# main.net
KiCad netlist of a schematic drawn in Altium Designer
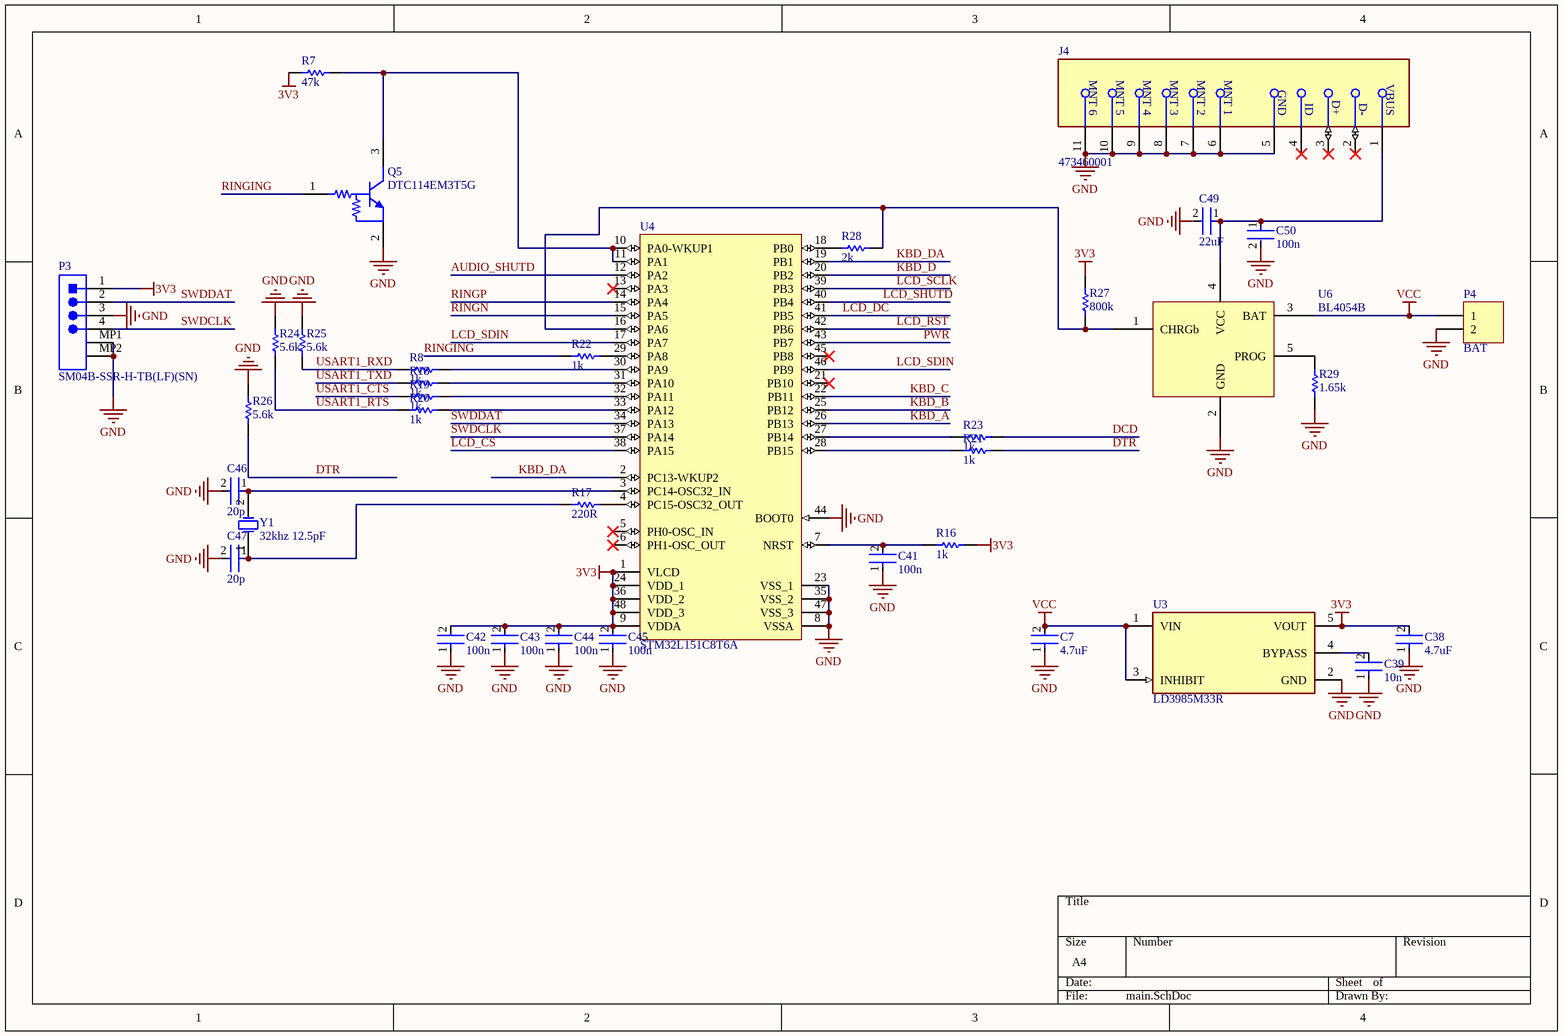
[diagram p0: main.SchDoc]

(export (version "E")
  (design (tool "Eeschema 10.0.6"))
  (components
    (comp (ref "C7")
      (value "4.7uF")
      (footprint "FP-GRM188-0_1-e0_2_0_55-IPC_A")
      (description "Chip Multilayer Ceramic Capacitors for General Purpose, 0603, 10uF, X5R, 15%, 20%, 6.3V")
      (fields (field (name "VOLTAGE") "6.3V") (field (name "TOLERANCE") "20%"))
      (libsource (lib "Altium Content Vault") (part "02cd4be3c70576c341d710602a673aa"))
    )
    (comp (ref "C38")
      (value "4.7uF")
      (footprint "FP-GRM188-0_1-e0_2_0_55-IPC_A")
      (description "Chip Multilayer Ceramic Capacitors for General Purpose, 0603, 10uF, X5R, 15%, 20%, 6.3V")
      (fields (field (name "VOLTAGE") "6.3V") (field (name "TOLERANCE") "20%"))
      (libsource (lib "Altium Content Vault") (part "02cd4be3c70576c341d710602a673aa"))
    )
    (comp (ref "C39")
      (value "10n")
      (footprint "FP-GRM155-0_05-IPC_A")
      (description "Chip Multilayer Ceramic Capacitors for General Purpose, 0402, 470pF, C0G, 30ppm/°C, 5%, 50V")
      (fields (field (name "VOLTAGE") "50V") (field (name "TOLERANCE") "5%"))
      (libsource (lib "Altium Content Vault") (part "02cd4be3c70576c341d710602a673aa"))
    )
    (comp (ref "C41")
      (value "100n")
      (footprint "FP-GRM155-0_05-IPC_A")
      (description "Chip Multilayer Ceramic Capacitors for General Purpose, 0402, 470pF, C0G, 30ppm/°C, 5%, 50V")
      (fields (field (name "VOLTAGE") "50V") (field (name "TOLERANCE") "5%"))
      (libsource (lib "Altium Content Vault") (part "02cd4be3c70576c341d710602a673aa"))
    )
    (comp (ref "C42")
      (value "100n")
      (footprint "FP-GRM155-0_05-IPC_A")
      (description "Chip Multilayer Ceramic Capacitors for General Purpose, 0402, 470pF, C0G, 30ppm/°C, 5%, 50V")
      (fields (field (name "VOLTAGE") "50V") (field (name "TOLERANCE") "5%"))
      (libsource (lib "Altium Content Vault") (part "02cd4be3c70576c341d710602a673aa"))
    )
    (comp (ref "C43")
      (value "100n")
      (footprint "FP-GRM155-0_05-IPC_A")
      (description "Chip Multilayer Ceramic Capacitors for General Purpose, 0402, 470pF, C0G, 30ppm/°C, 5%, 50V")
      (fields (field (name "VOLTAGE") "50V") (field (name "TOLERANCE") "5%"))
      (libsource (lib "Altium Content Vault") (part "02cd4be3c70576c341d710602a673aa"))
    )
    (comp (ref "C44")
      (value "100n")
      (footprint "FP-GRM155-0_05-IPC_A")
      (description "Chip Multilayer Ceramic Capacitors for General Purpose, 0402, 470pF, C0G, 30ppm/°C, 5%, 50V")
      (fields (field (name "VOLTAGE") "50V") (field (name "TOLERANCE") "5%"))
      (libsource (lib "Altium Content Vault") (part "02cd4be3c70576c341d710602a673aa"))
    )
    (comp (ref "C45")
      (value "100n")
      (footprint "FP-GRM155-0_05-IPC_A")
      (description "Chip Multilayer Ceramic Capacitors for General Purpose, 0402, 470pF, C0G, 30ppm/°C, 5%, 50V")
      (fields (field (name "VOLTAGE") "50V") (field (name "TOLERANCE") "5%"))
      (libsource (lib "Altium Content Vault") (part "02cd4be3c70576c341d710602a673aa"))
    )
    (comp (ref "C46")
      (value "20p")
      (footprint "FP-GRM155-0_05-IPC_A")
      (description "Chip Multilayer Ceramic Capacitors for General Purpose, 0402, 470pF, C0G, 30ppm/°C, 5%, 50V")
      (fields (field (name "VOLTAGE") "50V") (field (name "TOLERANCE") "5%"))
      (libsource (lib "Altium Content Vault") (part "02cd4be3c70576c341d710602a673aa"))
    )
    (comp (ref "C47")
      (value "20p")
      (footprint "FP-GRM155-0_05-IPC_A")
      (description "Chip Multilayer Ceramic Capacitors for General Purpose, 0402, 470pF, C0G, 30ppm/°C, 5%, 50V")
      (fields (field (name "VOLTAGE") "50V") (field (name "TOLERANCE") "5%"))
      (libsource (lib "Altium Content Vault") (part "02cd4be3c70576c341d710602a673aa"))
    )
    (comp (ref "C49")
      (value "22uF")
      (footprint "FP-GRM21B-0_15-MFG")
      (description "Chip Multilayer Ceramic Capacitors for General Purpose, 0805, 22uF, X5R, 15%, 20%, 6.3V")
      (fields (field (name "VOLTAGE") "6.3V") (field (name "TOLERANCE") "20%"))
      (libsource (lib "Altium Content Vault") (part "b4654b650e69147ec39a6b967a45e02"))
    )
    (comp (ref "C50")
      (value "100n")
      (footprint "FP-GRM155-0_05-IPC_A")
      (description "Chip Multilayer Ceramic Capacitors for General Purpose, 0402, 470pF, C0G, 30ppm/°C, 5%, 50V")
      (fields (field (name "VOLTAGE") "50V") (field (name "TOLERANCE") "5%"))
      (libsource (lib "Altium Content Vault") (part "02cd4be3c70576c341d710602a673aa"))
    )
    (comp (ref "J4")
      (value "473460001")
      (footprint "FP-473460001-MFG")
      (description "CONN RCPT USB2.0 MICRO B SMD R/A")
      (fields
        (field (name "OCTOPART") "https://octopart.com/47346-0001-molex-7164928")
        (field (name "MANUFACTURER") "Molex")
      )
      (libsource (lib "Altium Content Vault") (part "53ae1f1d9b557310b43ca686e5bb76a"))
    )
    (comp (ref "P3")
      (value "SM04B-SSR-H-TB(LF)(SN)")
      (footprint "JST-SM04B-SSR-H-TB_V")
      (description "SSR Connector, Pitch 1 mm, 1 x 4 Position, Height 2 mm, -20 to 85 degC, RoHS, Tape and Reel")
      (fields (field (name "MANUFACTURER") "JST"))
      (libsource (lib "Altium Content Vault") (part "CN-1P-2M-R4_A"))
    )
    (comp (ref "P4")
      (value "BAT")
      (footprint "HDR1X2")
      (description "Header, 2-Pin")
      (fields (field (name "PUBLISHER") "Altium Limited"))
      (libsource (lib "Miscellaneous Connectors") (part "Header 2"))
    )
    (comp (ref "Q5")
      (value "DTC114EM3T5G")
      (footprint "ONSC-SOT-723-3-631AA-01_V")
      (fields (field (name "MANUFACTURER") "On Semiconductor"))
      (libsource (lib "Altium Content Vault") (part "ONSC-BRT-NPN-B1E2C3-3"))
    )
    (comp (ref "R7")
      (value "47k")
      (footprint "RESC1005X40X25NL05T10")
      (fields (field (name "MANUFACTURER") "Yageo / Phycomp") (field (name "PART NUMBER") "RC0402JR-070RL"))
      (libsource (lib "Altium Content Vault") (part "RES"))
    )
    (comp (ref "R8")
      (value "1k")
      (footprint "RESC1005X40X25NL05T10")
      (fields (field (name "MANUFACTURER") "Yageo / Phycomp") (field (name "PART NUMBER") "RC0402JR-070RL"))
      (libsource (lib "Altium Content Vault") (part "RES"))
    )
    (comp (ref "R16")
      (value "1k")
      (footprint "RESC1005X40X25NL05T10")
      (fields (field (name "MANUFACTURER") "Yageo / Phycomp") (field (name "PART NUMBER") "RC0402JR-070RL"))
      (libsource (lib "Altium Content Vault") (part "RES"))
    )
    (comp (ref "R17")
      (value "220R")
      (footprint "RESC1005X40X25NL05T10")
      (fields (field (name "MANUFACTURER") "Yageo / Phycomp") (field (name "PART NUMBER") "RC0402JR-070RL"))
      (libsource (lib "Altium Content Vault") (part "RES"))
    )
    (comp (ref "R18")
      (value "1k")
      (footprint "RESC1005X40X25NL05T10")
      (fields (field (name "MANUFACTURER") "Yageo / Phycomp") (field (name "PART NUMBER") "RC0402JR-070RL"))
      (libsource (lib "Altium Content Vault") (part "RES"))
    )
    (comp (ref "R19")
      (value "1k")
      (footprint "RESC1005X40X25NL05T10")
      (fields (field (name "MANUFACTURER") "Yageo / Phycomp") (field (name "PART NUMBER") "RC0402JR-070RL"))
      (libsource (lib "Altium Content Vault") (part "RES"))
    )
    (comp (ref "R20")
      (value "1k")
      (footprint "RESC1005X40X25NL05T10")
      (fields (field (name "MANUFACTURER") "Yageo / Phycomp") (field (name "PART NUMBER") "RC0402JR-070RL"))
      (libsource (lib "Altium Content Vault") (part "RES"))
    )
    (comp (ref "R21")
      (value "1k")
      (footprint "RESC1005X40X25NL05T10")
      (fields (field (name "MANUFACTURER") "Yageo / Phycomp") (field (name "PART NUMBER") "RC0402JR-070RL"))
      (libsource (lib "Altium Content Vault") (part "RES"))
    )
    (comp (ref "R22")
      (value "1k")
      (footprint "RESC1005X40X25NL05T10")
      (fields (field (name "MANUFACTURER") "Yageo / Phycomp") (field (name "PART NUMBER") "RC0402JR-070RL"))
      (libsource (lib "Altium Content Vault") (part "RES"))
    )
    (comp (ref "R23")
      (value "1k")
      (footprint "RESC1005X40X25NL05T10")
      (fields (field (name "MANUFACTURER") "Yageo / Phycomp") (field (name "PART NUMBER") "RC0402JR-070RL"))
      (libsource (lib "Altium Content Vault") (part "RES"))
    )
    (comp (ref "R24")
      (value "5.6k")
      (footprint "RESC1005X40X25NL05T10")
      (fields (field (name "MANUFACTURER") "Yageo / Phycomp") (field (name "PART NUMBER") "RC0402JR-070RL"))
      (libsource (lib "Altium Content Vault") (part "RES"))
    )
    (comp (ref "R25")
      (value "5.6k")
      (footprint "RESC1005X40X25NL05T10")
      (fields (field (name "MANUFACTURER") "Yageo / Phycomp") (field (name "PART NUMBER") "RC0402JR-070RL"))
      (libsource (lib "Altium Content Vault") (part "RES"))
    )
    (comp (ref "R26")
      (value "5.6k")
      (footprint "RESC1005X40X25NL05T10")
      (fields (field (name "MANUFACTURER") "Yageo / Phycomp") (field (name "PART NUMBER") "RC0402JR-070RL"))
      (libsource (lib "Altium Content Vault") (part "RES"))
    )
    (comp (ref "R27")
      (value "800k")
      (footprint "RESC1005X40X25NL05T10")
      (fields (field (name "MANUFACTURER") "Yageo / Phycomp") (field (name "PART NUMBER") "RC0402JR-070RL"))
      (libsource (lib "Altium Content Vault") (part "RES"))
    )
    (comp (ref "R28")
      (value "2k")
      (footprint "RESC1005X40X25NL05T10")
      (fields (field (name "MANUFACTURER") "Yageo / Phycomp") (field (name "PART NUMBER") "RC0402JR-070RL"))
      (libsource (lib "Altium Content Vault") (part "RES"))
    )
    (comp (ref "R29")
      (value "1.65k")
      (footprint "RESC1005X40X25NL05T10")
      (fields (field (name "MANUFACTURER") "Yageo / Phycomp") (field (name "PART NUMBER") "RC0402JR-070RL"))
      (libsource (lib "Altium Content Vault") (part "RES"))
    )
    (comp (ref "U3")
      (value "LD3985M33R")
      (footprint "FP-SOT23-5L-7049676-MFG")
      (description "IC REG LINEAR 3.3V 150MA SOT23-5")
      (libsource (lib "Altium Content Vault") (part "aba04f4e281572ab958dbcc456c8333"))
    )
    (comp (ref "U4")
      (value "STM32L151C8T6A")
      (footprint "STM-LQFP48_M")
      (fields (field (name "MANUFACTURER") "STMicroelectronics"))
      (libsource (lib "Altium Content Vault") (part "MC-ARM-STM32L151_152-LQFP48"))
    )
    (comp (ref "U6") (value "BL4054B") (footprint "BL4054B") (libsource (lib "BL4054B") (part "Component_1")))
    (comp (ref "Y1")
      (value "32khz 12.5pF")
      (footprint "YT-26")
      (description "Crystal Oscillator")
      (fields (field (name "PUBLISHER") "Altium Limited"))
      (libsource (lib "Miscellaneous Devices") (part "XTAL"))
    )
  )
  (nets
    (net (code "1") (name "/AUDIO_SHUTD") (class "Default")
      (node (ref "U4") (pin "12") (pinfunction "PA2_12") (pintype "bidirectional"))
    )
    (net (code "2") (name "/DCD") (class "Default")
      (node (ref "R23") (pin "1") (pinfunction "1_1") (pintype "passive"))
    )
    (net (code "3") (name "/DTR") (class "Default")
      (node (ref "R21") (pin "2") (pinfunction "2_2") (pintype "passive"))
      (node (ref "R26") (pin "1") (pinfunction "1_1") (pintype "passive"))
    )
    (net (code "4") (name "/KBD_A") (class "Default")
      (node (ref "U4") (pin "26") (pinfunction "PB13_26") (pintype "bidirectional"))
    )
    (net (code "5") (name "/KBD_B") (class "Default")
      (node (ref "U4") (pin "25") (pinfunction "PB12_25") (pintype "bidirectional"))
    )
    (net (code "6") (name "/KBD_C") (class "Default")
      (node (ref "U4") (pin "22") (pinfunction "PB11_22") (pintype "bidirectional"))
    )
    (net (code "7") (name "/KBD_D") (class "Default")
      (node (ref "U4") (pin "20") (pinfunction "PB2_20") (pintype "bidirectional"))
    )
    (net (code "8") (name "/KBD_DA") (class "Default")
      (node (ref "U4") (pin "19") (pinfunction "PB1_19") (pintype "bidirectional"))
      (node (ref "U4") (pin "2") (pinfunction "PC13-WKUP2_2") (pintype "bidirectional"))
    )
    (net (code "9") (name "/LCD_CS") (class "Default")
      (node (ref "U4") (pin "38") (pinfunction "PA15_38") (pintype "bidirectional"))
    )
    (net (code "10") (name "/LCD_DC") (class "Default")
      (node (ref "U4") (pin "41") (pinfunction "PB5_41") (pintype "bidirectional"))
    )
    (net (code "11") (name "/LCD_RST") (class "Default")
      (node (ref "U4") (pin "42") (pinfunction "PB6_42") (pintype "bidirectional"))
    )
    (net (code "12") (name "/LCD_SCLK") (class "Default")
      (node (ref "U4") (pin "39") (pinfunction "PB3_39") (pintype "bidirectional"))
    )
    (net (code "13") (name "/LCD_SDIN") (class "Default")
      (node (ref "U4") (pin "17") (pinfunction "PA7_17") (pintype "bidirectional"))
      (node (ref "U4") (pin "46") (pinfunction "PB9_46") (pintype "bidirectional"))
    )
    (net (code "14") (name "/LCD_SHUTD") (class "Default")
      (node (ref "U4") (pin "40") (pinfunction "PB4_40") (pintype "bidirectional"))
    )
    (net (code "15") (name "/PWR") (class "Default")
      (node (ref "U4") (pin "43") (pinfunction "PB7_43") (pintype "bidirectional"))
    )
    (net (code "16") (name "/RINGING") (class "Default")
      (node (ref "Q5") (pin "1") (pinfunction "B_1") (pintype "passive"))
      (node (ref "R22") (pin "2") (pinfunction "2_2") (pintype "passive"))
    )
    (net (code "17") (name "/RINGN") (class "Default")
      (node (ref "U4") (pin "15") (pinfunction "PA5_15") (pintype "bidirectional"))
    )
    (net (code "18") (name "/RINGP") (class "Default")
      (node (ref "U4") (pin "14") (pinfunction "PA4_14") (pintype "bidirectional"))
    )
    (net (code "19") (name "/SWDCLK") (class "Default")
      (node (ref "P3") (pin "4") (pinfunction "4_4") (pintype "passive"))
      (node (ref "U4") (pin "37") (pinfunction "PA14_37") (pintype "bidirectional"))
    )
    (net (code "20") (name "/SWDDAT") (class "Default")
      (node (ref "P3") (pin "2") (pinfunction "2_2") (pintype "passive"))
      (node (ref "U4") (pin "34") (pinfunction "PA13_34") (pintype "bidirectional"))
    )
    (net (code "21") (name "/USART1_CTS") (class "Default")
      (node (ref "R19") (pin "1") (pinfunction "1_1") (pintype "passive"))
    )
    (net (code "22") (name "/USART1_RTS") (class "Default")
      (node (ref "R20") (pin "1") (pinfunction "1_1") (pintype "passive"))
      (node (ref "R24") (pin "1") (pinfunction "1_1") (pintype "passive"))
    )
    (net (code "23") (name "/USART1_RXD") (class "Default")
      (node (ref "R25") (pin "1") (pinfunction "1_1") (pintype "passive"))
      (node (ref "R8") (pin "1") (pinfunction "1_1") (pintype "passive"))
    )
    (net (code "24") (name "/USART1_TXD") (class "Default")
      (node (ref "R18") (pin "1") (pinfunction "1_1") (pintype "passive"))
    )
    (net (code "25") (name "3V3") (class "Default")
      (node (ref "C38") (pin "2") (pinfunction "2_2") (pintype "passive"))
      (node (ref "C42") (pin "2") (pinfunction "2_2") (pintype "passive"))
      (node (ref "C43") (pin "2") (pinfunction "2_2") (pintype "passive"))
      (node (ref "C44") (pin "2") (pinfunction "2_2") (pintype "passive"))
      (node (ref "C45") (pin "2") (pinfunction "2_2") (pintype "passive"))
      (node (ref "P3") (pin "1") (pinfunction "1_1") (pintype "passive"))
      (node (ref "R16") (pin "1") (pinfunction "1_1") (pintype "passive"))
      (node (ref "R27") (pin "2") (pinfunction "2_2") (pintype "passive"))
      (node (ref "R7") (pin "2") (pinfunction "2_2") (pintype "passive"))
      (node (ref "U3") (pin "5") (pinfunction "VOUT_5") (pintype "passive"))
      (node (ref "U4") (pin "1") (pinfunction "VLCD_1") (pintype "power_in"))
      (node (ref "U4") (pin "24") (pinfunction "VDD_1_24") (pintype "power_in"))
      (node (ref "U4") (pin "36") (pinfunction "VDD_2_36") (pintype "power_in"))
      (node (ref "U4") (pin "48") (pinfunction "VDD_3_48") (pintype "power_in"))
      (node (ref "U4") (pin "9") (pinfunction "VDDA_9") (pintype "power_in"))
    )
    (net (code "26") (name "GND") (class "Default")
      (node (ref "C38") (pin "1") (pinfunction "1_1") (pintype "passive"))
      (node (ref "C39") (pin "1") (pinfunction "1_1") (pintype "passive"))
      (node (ref "C41") (pin "1") (pinfunction "1_1") (pintype "passive"))
      (node (ref "C42") (pin "1") (pinfunction "1_1") (pintype "passive"))
      (node (ref "C43") (pin "1") (pinfunction "1_1") (pintype "passive"))
      (node (ref "C44") (pin "1") (pinfunction "1_1") (pintype "passive"))
      (node (ref "C45") (pin "1") (pinfunction "1_1") (pintype "passive"))
      (node (ref "C46") (pin "2") (pinfunction "2_2") (pintype "passive"))
      (node (ref "C47") (pin "2") (pinfunction "2_2") (pintype "passive"))
      (node (ref "C49") (pin "2") (pinfunction "2_2") (pintype "passive"))
      (node (ref "C50") (pin "2") (pinfunction "2_2") (pintype "passive"))
      (node (ref "C7") (pin "1") (pinfunction "1_1") (pintype "passive"))
      (node (ref "J4") (pin "10") (pinfunction "MNT_5_10") (pintype "passive"))
      (node (ref "J4") (pin "11") (pinfunction "MNT_6_11") (pintype "passive"))
      (node (ref "J4") (pin "5") (pinfunction "GND_5") (pintype "power_in"))
      (node (ref "J4") (pin "6") (pinfunction "MNT_1_6") (pintype "passive"))
      (node (ref "J4") (pin "7") (pinfunction "MNT_2_7") (pintype "passive"))
      (node (ref "J4") (pin "8") (pinfunction "MNT_3_8") (pintype "passive"))
      (node (ref "J4") (pin "9") (pinfunction "MNT_4_9") (pintype "passive"))
      (node (ref "P3") (pin "3") (pinfunction "3_3") (pintype "passive"))
      (node (ref "P3") (pin "MP1") (pinfunction "MP1_MP1") (pintype "passive"))
      (node (ref "P3") (pin "MP2") (pinfunction "MP2_MP2") (pintype "passive"))
      (node (ref "P4") (pin "2") (pinfunction "2_2") (pintype "passive"))
      (node (ref "Q5") (pin "2") (pinfunction "E_2") (pintype "passive"))
      (node (ref "R24") (pin "2") (pinfunction "2_2") (pintype "passive"))
      (node (ref "R25") (pin "2") (pinfunction "2_2") (pintype "passive"))
      (node (ref "R26") (pin "2") (pinfunction "2_2") (pintype "passive"))
      (node (ref "R29") (pin "2") (pinfunction "2_2") (pintype "passive"))
      (node (ref "U3") (pin "2") (pinfunction "GND_2") (pintype "power_in"))
      (node (ref "U4") (pin "23") (pinfunction "VSS_1_23") (pintype "power_in"))
      (node (ref "U4") (pin "35") (pinfunction "VSS_2_35") (pintype "power_in"))
      (node (ref "U4") (pin "44") (pinfunction "BOOT0_44") (pintype "input"))
      (node (ref "U4") (pin "47") (pinfunction "VSS_3_47") (pintype "power_in"))
      (node (ref "U4") (pin "8") (pinfunction "VSSA_8") (pintype "power_in"))
      (node (ref "U6") (pin "2") (pinfunction "GND_2") (pintype "passive"))
    )
    (net (code "27") (name "Net-(J4-VBUS)") (class "Default")
      (node (ref "C49") (pin "1") (pinfunction "1_1") (pintype "passive"))
      (node (ref "C50") (pin "1") (pinfunction "1_1") (pintype "passive"))
      (node (ref "J4") (pin "1") (pinfunction "VBUS_1") (pintype "power_in"))
      (node (ref "U6") (pin "4") (pinfunction "VCC_4") (pintype "passive"))
    )
    (net (code "28") (name "Net-(Q5-C)") (class "Default")
      (node (ref "Q5") (pin "3") (pinfunction "C_3") (pintype "passive"))
      (node (ref "R7") (pin "1") (pinfunction "1_1") (pintype "passive"))
      (node (ref "U4") (pin "10") (pinfunction "PA0-WKUP1_10") (pintype "bidirectional"))
      (node (ref "U4") (pin "11") (pinfunction "PA1_11") (pintype "bidirectional"))
    )
    (net (code "29") (name "Net-(U3-BYPASS)") (class "Default")
      (node (ref "C39") (pin "2") (pinfunction "2_2") (pintype "passive"))
      (node (ref "U3") (pin "4") (pinfunction "BYPASS_4") (pintype "passive"))
    )
    (net (code "30") (name "Net-(U4-NRST)") (class "Default")
      (node (ref "C41") (pin "2") (pinfunction "2_2") (pintype "passive"))
      (node (ref "R16") (pin "2") (pinfunction "2_2") (pintype "passive"))
      (node (ref "U4") (pin "7") (pinfunction "NRST_7") (pintype "bidirectional"))
    )
    (net (code "31") (name "Net-(U4-PA6)") (class "Default")
      (node (ref "R27") (pin "1") (pinfunction "1_1") (pintype "passive"))
      (node (ref "R28") (pin "1") (pinfunction "1_1") (pintype "passive"))
      (node (ref "U4") (pin "16") (pinfunction "PA6_16") (pintype "bidirectional"))
      (node (ref "U6") (pin "1") (pinfunction "CHRGb_1") (pintype "passive"))
    )
    (net (code "32") (name "Net-(U4-PA8)") (class "Default")
      (node (ref "R22") (pin "1") (pinfunction "1_1") (pintype "passive"))
      (node (ref "U4") (pin "29") (pinfunction "PA8_29") (pintype "bidirectional"))
    )
    (net (code "33") (name "Net-(U4-PA9)") (class "Default")
      (node (ref "R8") (pin "2") (pinfunction "2_2") (pintype "passive"))
      (node (ref "U4") (pin "30") (pinfunction "PA9_30") (pintype "bidirectional"))
    )
    (net (code "34") (name "Net-(U4-PA10)") (class "Default")
      (node (ref "R18") (pin "2") (pinfunction "2_2") (pintype "passive"))
      (node (ref "U4") (pin "31") (pinfunction "PA10_31") (pintype "bidirectional"))
    )
    (net (code "35") (name "Net-(U4-PA11)") (class "Default")
      (node (ref "R19") (pin "2") (pinfunction "2_2") (pintype "passive"))
      (node (ref "U4") (pin "32") (pinfunction "PA11_32") (pintype "bidirectional"))
    )
    (net (code "36") (name "Net-(U4-PA12)") (class "Default")
      (node (ref "R20") (pin "2") (pinfunction "2_2") (pintype "passive"))
      (node (ref "U4") (pin "33") (pinfunction "PA12_33") (pintype "bidirectional"))
    )
    (net (code "37") (name "Net-(U4-PB0)") (class "Default")
      (node (ref "R28") (pin "2") (pinfunction "2_2") (pintype "passive"))
      (node (ref "U4") (pin "18") (pinfunction "PB0_18") (pintype "bidirectional"))
    )
    (net (code "38") (name "Net-(U4-PB14)") (class "Default")
      (node (ref "R23") (pin "2") (pinfunction "2_2") (pintype "passive"))
      (node (ref "U4") (pin "27") (pinfunction "PB14_27") (pintype "bidirectional"))
    )
    (net (code "39") (name "Net-(U4-PB15)") (class "Default")
      (node (ref "R21") (pin "1") (pinfunction "1_1") (pintype "passive"))
      (node (ref "U4") (pin "28") (pinfunction "PB15_28") (pintype "bidirectional"))
    )
    (net (code "40") (name "Net-(U4-PC14-OSC32_IN)") (class "Default")
      (node (ref "C46") (pin "1") (pinfunction "1_1") (pintype "passive"))
      (node (ref "U4") (pin "3") (pinfunction "PC14-OSC32_IN_3") (pintype "bidirectional"))
      (node (ref "Y1") (pin "2") (pinfunction "OSC2_2") (pintype "passive"))
    )
    (net (code "41") (name "Net-(U4-PC15-OSC32_OUT)") (class "Default")
      (node (ref "R17") (pin "2") (pinfunction "2_2") (pintype "passive"))
      (node (ref "U4") (pin "4") (pinfunction "PC15-OSC32_OUT_4") (pintype "bidirectional"))
    )
    (net (code "42") (name "Net-(U6-PROG)") (class "Default")
      (node (ref "R29") (pin "1") (pinfunction "1_1") (pintype "passive"))
      (node (ref "U6") (pin "5") (pinfunction "PROG_5") (pintype "passive"))
    )
    (net (code "43") (name "Net-(Y1-OSC1)") (class "Default")
      (node (ref "C47") (pin "1") (pinfunction "1_1") (pintype "passive"))
      (node (ref "R17") (pin "1") (pinfunction "1_1") (pintype "passive"))
      (node (ref "Y1") (pin "1") (pinfunction "OSC1_1") (pintype "passive"))
    )
    (net (code "44") (name "VCC") (class "Default")
      (node (ref "C7") (pin "2") (pinfunction "2_2") (pintype "passive"))
      (node (ref "P4") (pin "1") (pinfunction "1_1") (pintype "passive"))
      (node (ref "U3") (pin "1") (pinfunction "VIN_1") (pintype "power_in"))
      (node (ref "U3") (pin "3") (pinfunction "INHIBIT_3") (pintype "input"))
      (node (ref "U6") (pin "3") (pinfunction "BAT_3") (pintype "passive"))
    )
    (net (code "45") (name "unconnected-(J4-D+-Pad3)") (class "Default")
      (node (ref "J4") (pin "3") (pinfunction "D+_3") (pintype "bidirectional+no_connect"))
    )
    (net (code "46") (name "unconnected-(J4-D--Pad2)") (class "Default")
      (node (ref "J4") (pin "2") (pinfunction "D-_2") (pintype "bidirectional+no_connect"))
    )
    (net (code "47") (name "unconnected-(J4-ID-Pad4)") (class "Default")
      (node (ref "J4") (pin "4") (pinfunction "ID_4") (pintype "passive+no_connect"))
    )
    (net (code "48") (name "unconnected-(U4-PA3-Pad13)") (class "Default")
      (node (ref "U4") (pin "13") (pinfunction "PA3_13") (pintype "bidirectional+no_connect"))
    )
    (net (code "49") (name "unconnected-(U4-PB8-Pad45)") (class "Default")
      (node (ref "U4") (pin "45") (pinfunction "PB8_45") (pintype "bidirectional+no_connect"))
    )
    (net (code "50") (name "unconnected-(U4-PB10-Pad21)") (class "Default")
      (node (ref "U4") (pin "21") (pinfunction "PB10_21") (pintype "bidirectional+no_connect"))
    )
    (net (code "51") (name "unconnected-(U4-PH0-OSC_IN-Pad5)") (class "Default")
      (node (ref "U4") (pin "5") (pinfunction "PH0-OSC_IN_5") (pintype "bidirectional+no_connect"))
    )
    (net (code "52") (name "unconnected-(U4-PH1-OSC_OUT-Pad6)") (class "Default")
      (node (ref "U4") (pin "6") (pinfunction "PH1-OSC_OUT_6") (pintype "bidirectional+no_connect"))
    )
  )
)
